# MiniSys.net
KiCad netlist of a schematic drawn in Altium Designer
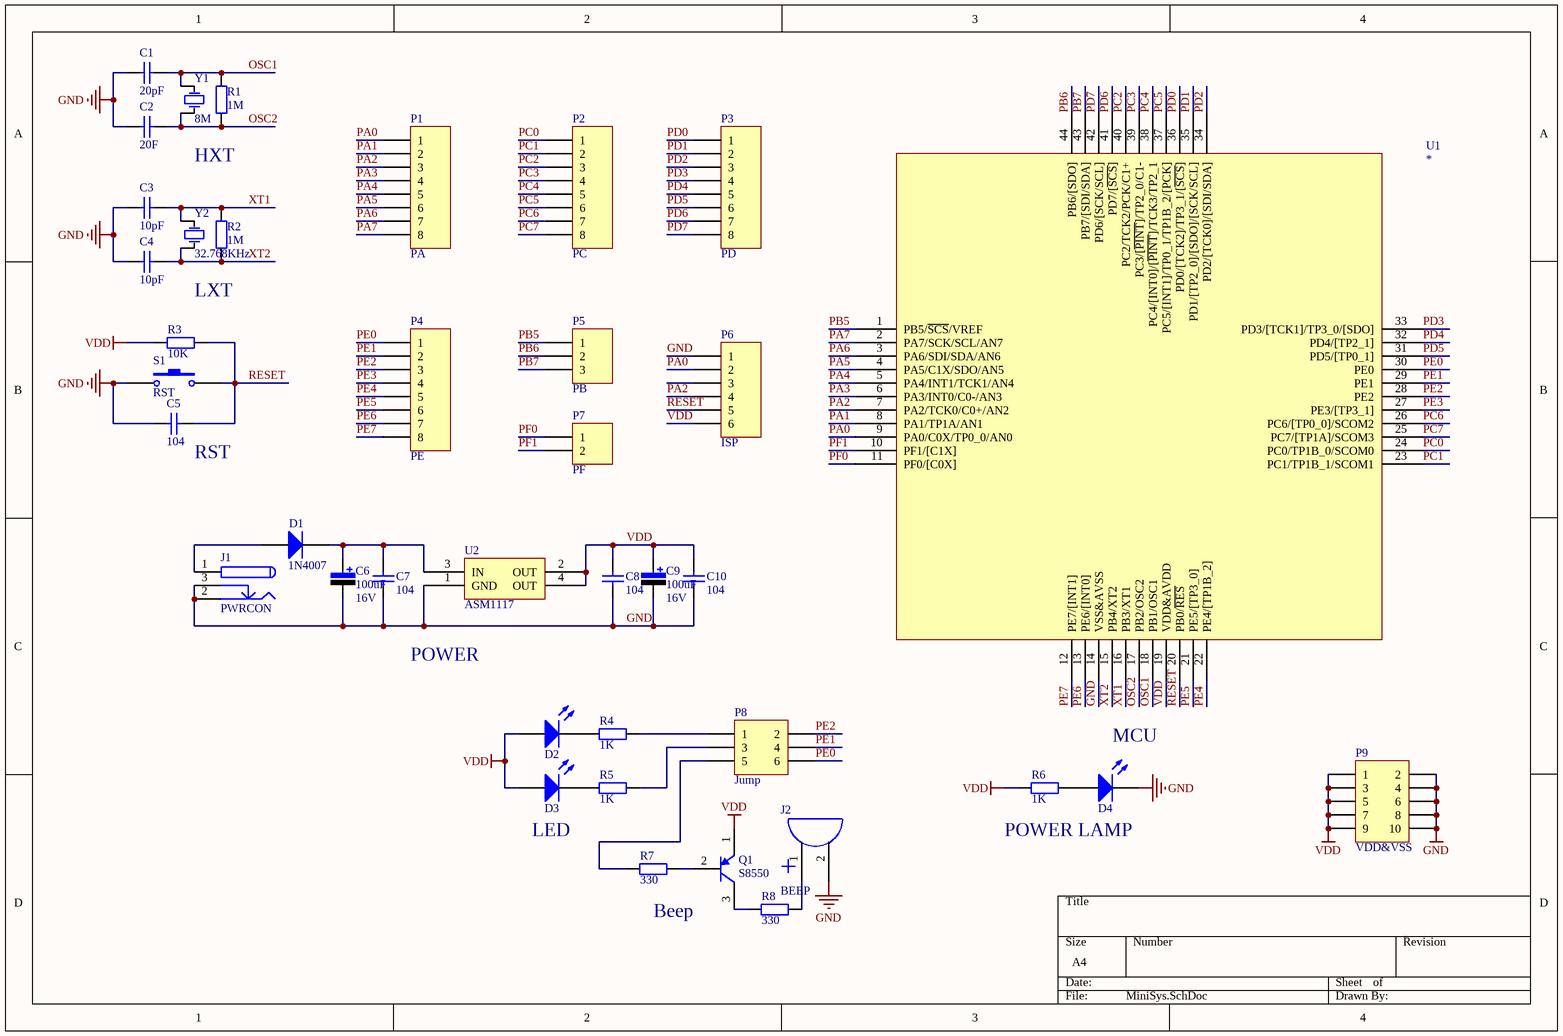
[diagram p0: MiniSys.SchDoc]

(export (version "E")
  (design (tool "Eeschema 10.0.6"))
  (components
    (comp (ref "C1")
      (value "20pF")
      (footprint "C-RAD-0805")
      (description "无极性电容")
      (fields (field (name "Comment") "Cap") (field (name "PUBLISHER") "Altium Limited"))
      (libsource (lib "Library") (part "Cap"))
    )
    (comp (ref "C2")
      (value "20F")
      (footprint "C-RAD-0805")
      (description "无极性电容")
      (fields (field (name "Comment") "Cap") (field (name "PUBLISHER") "Altium Limited"))
      (libsource (lib "Library") (part "Cap"))
    )
    (comp (ref "C3")
      (value "10pF")
      (footprint "C-RAD-0805")
      (description "无极性电容")
      (fields (field (name "Comment") "Cap") (field (name "PUBLISHER") "Altium Limited"))
      (libsource (lib "Library") (part "Cap"))
    )
    (comp (ref "C4")
      (value "10pF")
      (footprint "C-RAD-0805")
      (description "无极性电容")
      (fields (field (name "Comment") "Cap") (field (name "PUBLISHER") "Altium Limited"))
      (libsource (lib "Library") (part "Cap"))
    )
    (comp (ref "C5")
      (value "104")
      (footprint "C-RAD-0805")
      (description "无极性电容")
      (fields (field (name "Comment") "Cap") (field (name "PUBLISHER") "Altium Limited"))
      (libsource (lib "Library") (part "Cap"))
    )
    (comp (ref "C6")
      (value "100uF")
      (footprint "RB.1/.2")
      (description "极性电解电容")
      (fields
        (field (name "VOL") "16V")
        (field (name "Comment") "Cap Pol")
        (field (name "PUBLISHER") "Altium Limited")
      )
      (libsource (lib "Library") (part "Cap Pol"))
    )
    (comp (ref "C7")
      (value "104")
      (footprint "C-RAD-0805")
      (description "无极性电容")
      (fields (field (name "Comment") "Cap") (field (name "PUBLISHER") "Altium Limited"))
      (libsource (lib "Library") (part "Cap"))
    )
    (comp (ref "C8")
      (value "104")
      (footprint "C-RAD-0805")
      (description "无极性电容")
      (fields (field (name "Comment") "Cap") (field (name "PUBLISHER") "Altium Limited"))
      (libsource (lib "Library") (part "Cap"))
    )
    (comp (ref "C9")
      (value "100uF")
      (footprint "RB.1/.2")
      (description "极性电解电容")
      (fields
        (field (name "VOL") "16V")
        (field (name "Comment") "Cap Pol")
        (field (name "PUBLISHER") "Altium Limited")
      )
      (libsource (lib "Library") (part "Cap Pol"))
    )
    (comp (ref "C10")
      (value "104")
      (footprint "C-RAD-0805")
      (description "无极性电容")
      (fields (field (name "Comment") "Cap") (field (name "PUBLISHER") "Altium Limited"))
      (libsource (lib "Library") (part "Cap"))
    )
    (comp (ref "D1")
      (value "Diode")
      (footprint "DIODE-AXL")
      (description "二极管")
      (fields (field (name "TYPE") "1N4007") (field (name "PUBLISHER") "Altium Limited"))
      (libsource (lib "Library") (part "Diode"))
    )
    (comp (ref "D2")
      (value "LED0")
      (footprint "LED_0805")
      (description "发光二极管")
      (fields (field (name "PUBLISHER") "Altium Limited"))
      (libsource (lib "Library") (part "LED0"))
    )
    (comp (ref "D3")
      (value "LED0")
      (footprint "LED_0805")
      (description "发光二极管")
      (fields (field (name "PUBLISHER") "Altium Limited"))
      (libsource (lib "Library") (part "LED0"))
    )
    (comp (ref "D4")
      (value "LED0")
      (footprint "LED_0805")
      (description "发光二极管")
      (fields (field (name "PUBLISHER") "Altium Limited"))
      (libsource (lib "Library") (part "LED0"))
    )
    (comp (ref "J1")
      (value "PWRCON")
      (footprint "DC-005")
      (description "直流电源端子")
      (fields (field (name "PUBLISHER") "Altium Limited"))
      (libsource (lib "Library") (part "PWRCON"))
    )
    (comp (ref "J2")
      (value "BEEP")
      (footprint "Beep")
      (description "蜂鸣器")
      (libsource (lib "Library") (part "BEEP"))
    )
    (comp (ref "P1")
      (value "PA")
      (footprint "HDR1X8")
      (description "Header, 8-Pin")
      (fields (field (name "PUBLISHER") "Altium Limited"))
      (libsource (lib "Library") (part "Header 8"))
    )
    (comp (ref "P2")
      (value "PC")
      (footprint "HDR1X8")
      (description "Header, 8-Pin")
      (fields (field (name "PUBLISHER") "Altium Limited"))
      (libsource (lib "Library") (part "Header 8"))
    )
    (comp (ref "P3")
      (value "PD")
      (footprint "HDR1X8")
      (description "Header, 8-Pin")
      (fields (field (name "PUBLISHER") "Altium Limited"))
      (libsource (lib "Library") (part "Header 8"))
    )
    (comp (ref "P4")
      (value "PE")
      (footprint "HDR1X8")
      (description "Header, 8-Pin")
      (fields (field (name "PUBLISHER") "Altium Limited"))
      (libsource (lib "Library") (part "Header 8"))
    )
    (comp (ref "P5")
      (value "PB")
      (footprint "HDR3X1_A")
      (description "接插件")
      (fields (field (name "PUBLISHER") "Altium Limited"))
      (libsource (lib "Library") (part "Header 3"))
    )
    (comp (ref "P6")
      (value "ISP")
      (footprint "HDR1X6")
      (description "接插件")
      (fields (field (name "PUBLISHER") "Altium Limited"))
      (libsource (lib "Library") (part "Header 6"))
    )
    (comp (ref "P7")
      (value "PF")
      (footprint "HDR2X1_A")
      (description "接插件")
      (fields (field (name "PUBLISHER") "Altium Limited"))
      (libsource (lib "Library") (part "Header 2"))
    )
    (comp (ref "P8")
      (value "Jump")
      (footprint "HDR2X3")
      (description "Header, 3-Pin, Dual row")
      (fields (field (name "PUBLISHER") "Altium Limited"))
      (libsource (lib "Miscellaneous Connectors") (part "Header 3X2"))
    )
    (comp (ref "P9")
      (value "VDD&VSS")
      (footprint "HDR5X2_A1")
      (description "接插件")
      (fields (field (name "PUBLISHER") "Altium Limited"))
      (libsource (lib "Library") (part "Header 5X2"))
    )
    (comp (ref "Q1")
      (value "S8550")
      (footprint "TO-92A")
      (description "PNP三极管")
      (fields (field (name "PUBLISHER") "Altium Limited"))
      (libsource (lib "Library") (part "S8550"))
    )
    (comp (ref "R1")
      (value "1M")
      (footprint "0805-1")
      (description "贴片电阻")
      (fields (field (name "Comment") "Res1") (field (name "PUBLISHER") "Altium Limited"))
      (libsource (lib "Library") (part "Res1"))
    )
    (comp (ref "R2")
      (value "1M")
      (footprint "0805-1")
      (description "贴片电阻")
      (fields (field (name "Comment") "Res1") (field (name "PUBLISHER") "Altium Limited"))
      (libsource (lib "Library") (part "Res1"))
    )
    (comp (ref "R3")
      (value "10K")
      (footprint "0805-1")
      (description "贴片电阻")
      (fields (field (name "Comment") "Res1") (field (name "PUBLISHER") "Altium Limited"))
      (libsource (lib "") (part "Res1_2"))
    )
    (comp (ref "R4")
      (value "1K")
      (footprint "0805-1")
      (description "贴片电阻")
      (fields (field (name "Comment") "Res1") (field (name "PUBLISHER") "Altium Limited"))
      (libsource (lib "") (part "Res1_2"))
    )
    (comp (ref "R5")
      (value "1K")
      (footprint "0805-1")
      (description "贴片电阻")
      (fields (field (name "Comment") "Res1") (field (name "PUBLISHER") "Altium Limited"))
      (libsource (lib "") (part "Res1_2"))
    )
    (comp (ref "R6")
      (value "1K")
      (footprint "0805-1")
      (description "贴片电阻")
      (fields (field (name "Comment") "Res1") (field (name "PUBLISHER") "Altium Limited"))
      (libsource (lib "") (part "Res1_2"))
    )
    (comp (ref "R7")
      (value "330")
      (footprint "0805-1")
      (description "贴片电阻")
      (fields (field (name "Comment") "Res1") (field (name "PUBLISHER") "Altium Limited"))
      (libsource (lib "") (part "Res1_2"))
    )
    (comp (ref "R8")
      (value "330")
      (footprint "0805-1")
      (description "贴片电阻")
      (fields (field (name "Comment") "Res1") (field (name "PUBLISHER") "Altium Limited"))
      (libsource (lib "") (part "Res1_1"))
    )
    (comp (ref "S1")
      (value "RST")
      (footprint "BUTTON")
      (description "微动开关")
      (fields (field (name "PUBLISHER") "Altium Limited"))
      (libsource (lib "Library") (part "SW-PB"))
    )
    (comp (ref "U1")
      (value "*")
      (description "HT66F50 LQPF44")
      (fields (field (name "NAME") "*"))
      (libsource (lib "HT66FU50") (part "HT66FXXX"))
    )
    (comp (ref "U2")
      (value "ASM1117")
      (footprint "SOT-223")
      (description "3.3V稳压芯片")
      (libsource (lib "Library") (part "ASM1117"))
    )
    (comp (ref "Y1")
      (value "8M")
      (footprint "X-HC49U")
      (description "晶振")
      (fields (field (name "Comment") "XTAL") (field (name "PUBLISHER") "Altium Limited"))
      (libsource (lib "Library") (part "XTAL"))
    )
    (comp (ref "Y2")
      (value "32.768KHz")
      (footprint "X-TC15")
      (description "晶振")
      (fields (field (name "Comment") "XTAL") (field (name "PUBLISHER") "Altium Limited"))
      (libsource (lib "Library") (part "XTAL"))
    )
  )
  (nets
    (net (code "1") (name "/OSC1") (class "Default")
      (node (ref "C1") (pin "1") (pinfunction "1_1") (pintype "passive"))
      (node (ref "R1") (pin "1") (pinfunction "1_1") (pintype "passive"))
      (node (ref "U1") (pin "18") (pinfunction "PB1/OSC1_18") (pintype "passive"))
      (node (ref "Y1") (pin "1") (pinfunction "OSC1_1") (pintype "passive"))
    )
    (net (code "2") (name "/OSC2") (class "Default")
      (node (ref "C2") (pin "1") (pinfunction "1_1") (pintype "passive"))
      (node (ref "R1") (pin "2") (pinfunction "2_2") (pintype "passive"))
      (node (ref "U1") (pin "17") (pinfunction "PB2/OSC2_17") (pintype "passive"))
      (node (ref "Y1") (pin "2") (pinfunction "OSC2_2") (pintype "passive"))
    )
    (net (code "3") (name "/PA0") (class "Default")
      (node (ref "P1") (pin "1") (pinfunction "1_1") (pintype "passive"))
      (node (ref "P6") (pin "2") (pinfunction "2_2") (pintype "passive"))
      (node (ref "U1") (pin "9") (pinfunction "PA0/C0X/TP0_0/AN0_9") (pintype "passive"))
    )
    (net (code "4") (name "/PA1") (class "Default")
      (node (ref "P1") (pin "2") (pinfunction "2_2") (pintype "passive"))
      (node (ref "U1") (pin "8") (pinfunction "PA1/TP1A/AN1_8") (pintype "passive"))
    )
    (net (code "5") (name "/PA2") (class "Default")
      (node (ref "P1") (pin "3") (pinfunction "3_3") (pintype "passive"))
      (node (ref "P6") (pin "4") (pinfunction "4_4") (pintype "passive"))
      (node (ref "U1") (pin "7") (pinfunction "PA2/TCK0/C0+/AN2_7") (pintype "passive"))
    )
    (net (code "6") (name "/PA3") (class "Default")
      (node (ref "P1") (pin "4") (pinfunction "4_4") (pintype "passive"))
      (node (ref "U1") (pin "6") (pinfunction "PA3/INT0/C0-/AN3_6") (pintype "passive"))
    )
    (net (code "7") (name "/PA4") (class "Default")
      (node (ref "P1") (pin "5") (pinfunction "5_5") (pintype "passive"))
      (node (ref "U1") (pin "5") (pinfunction "PA4/INT1/TCK1/AN4_5") (pintype "passive"))
    )
    (net (code "8") (name "/PA5") (class "Default")
      (node (ref "P1") (pin "6") (pinfunction "6_6") (pintype "passive"))
      (node (ref "U1") (pin "4") (pinfunction "PA5/C1X/SDO/AN5_4") (pintype "passive"))
    )
    (net (code "9") (name "/PA6") (class "Default")
      (node (ref "P1") (pin "7") (pinfunction "7_7") (pintype "passive"))
      (node (ref "U1") (pin "3") (pinfunction "PA6/SDI/SDA/AN6_3") (pintype "passive"))
    )
    (net (code "10") (name "/PA7") (class "Default")
      (node (ref "P1") (pin "8") (pinfunction "8_8") (pintype "passive"))
      (node (ref "U1") (pin "2") (pinfunction "PA7/SCK/SCL/AN7_2") (pintype "passive"))
    )
    (net (code "11") (name "/PB5") (class "Default")
      (node (ref "P5") (pin "1") (pinfunction "1_1") (pintype "passive"))
      (node (ref "U1") (pin "1") (pinfunction "PB5/~{SCS}/VREF_1") (pintype "passive"))
    )
    (net (code "12") (name "/PB6") (class "Default")
      (node (ref "P5") (pin "2") (pinfunction "2_2") (pintype "passive"))
      (node (ref "U1") (pin "44") (pinfunction "PB6/[SDO]_44") (pintype "passive"))
    )
    (net (code "13") (name "/PB7") (class "Default")
      (node (ref "P5") (pin "3") (pinfunction "3_3") (pintype "passive"))
      (node (ref "U1") (pin "43") (pinfunction "PB7/[SDI/SDA]_43") (pintype "passive"))
    )
    (net (code "14") (name "/PC0") (class "Default")
      (node (ref "P2") (pin "1") (pinfunction "1_1") (pintype "passive"))
      (node (ref "U1") (pin "24") (pinfunction "PC0/TP1B_0/SCOM0_24") (pintype "passive"))
    )
    (net (code "15") (name "/PC1") (class "Default")
      (node (ref "P2") (pin "2") (pinfunction "2_2") (pintype "passive"))
      (node (ref "U1") (pin "23") (pinfunction "PC1/TP1B_1/SCOM1_23") (pintype "passive"))
    )
    (net (code "16") (name "/PC2") (class "Default")
      (node (ref "P2") (pin "3") (pinfunction "3_3") (pintype "passive"))
      (node (ref "U1") (pin "40") (pinfunction "PC2/TCK2/PCK/C1+_40") (pintype "passive"))
    )
    (net (code "17") (name "/PC3") (class "Default")
      (node (ref "P2") (pin "4") (pinfunction "4_4") (pintype "passive"))
      (node (ref "U1") (pin "39") (pinfunction "PC3/[~{PINT}]/TP2_0/C1-_39") (pintype "passive"))
    )
    (net (code "18") (name "/PC4") (class "Default")
      (node (ref "P2") (pin "5") (pinfunction "5_5") (pintype "passive"))
      (node (ref "U1") (pin "38") (pinfunction "PC4/[INT0]/[~{PINT}]/TCK3/TP2_1_38") (pintype "passive"))
    )
    (net (code "19") (name "/PC5") (class "Default")
      (node (ref "P2") (pin "6") (pinfunction "6_6") (pintype "passive"))
      (node (ref "U1") (pin "37") (pinfunction "PC5/[INT1]/TP0_1/TP1B_2/[PCK]_37") (pintype "passive"))
    )
    (net (code "20") (name "/PC6") (class "Default")
      (node (ref "P2") (pin "7") (pinfunction "7_7") (pintype "passive"))
      (node (ref "U1") (pin "26") (pinfunction "PC6/[TP0_0]/SCOM2_26") (pintype "passive"))
    )
    (net (code "21") (name "/PC7") (class "Default")
      (node (ref "P2") (pin "8") (pinfunction "8_8") (pintype "passive"))
      (node (ref "U1") (pin "25") (pinfunction "PC7/[TP1A]/SCOM3_25") (pintype "passive"))
    )
    (net (code "22") (name "/PD0") (class "Default")
      (node (ref "P3") (pin "1") (pinfunction "1_1") (pintype "passive"))
      (node (ref "U1") (pin "36") (pinfunction "PD0/[TCK2]/TP3_1/[~{SCS}]_36") (pintype "passive"))
    )
    (net (code "23") (name "/PD1") (class "Default")
      (node (ref "P3") (pin "2") (pinfunction "2_2") (pintype "passive"))
      (node (ref "U1") (pin "35") (pinfunction "PD1/[TP2_0]/[SDO]/[SCK/SCL]_35") (pintype "passive"))
    )
    (net (code "24") (name "/PD2") (class "Default")
      (node (ref "P3") (pin "3") (pinfunction "3_3") (pintype "passive"))
      (node (ref "U1") (pin "34") (pinfunction "PD2/[TCK0]/[SDI/SDA]_34") (pintype "passive"))
    )
    (net (code "25") (name "/PD3") (class "Default")
      (node (ref "P3") (pin "4") (pinfunction "4_4") (pintype "passive"))
      (node (ref "U1") (pin "33") (pinfunction "PD3/[TCK1]/TP3_0/[SDO]_33") (pintype "passive"))
    )
    (net (code "26") (name "/PD4") (class "Default")
      (node (ref "P3") (pin "5") (pinfunction "5_5") (pintype "passive"))
      (node (ref "U1") (pin "32") (pinfunction "PD4/[TP2_1]_32") (pintype "passive"))
    )
    (net (code "27") (name "/PD5") (class "Default")
      (node (ref "P3") (pin "6") (pinfunction "6_6") (pintype "passive"))
      (node (ref "U1") (pin "31") (pinfunction "PD5/[TP0_1]_31") (pintype "passive"))
    )
    (net (code "28") (name "/PD6") (class "Default")
      (node (ref "P3") (pin "7") (pinfunction "7_7") (pintype "passive"))
      (node (ref "U1") (pin "41") (pinfunction "PD7/[~{SCS}]_41") (pintype "passive"))
    )
    (net (code "29") (name "/PD7") (class "Default")
      (node (ref "P3") (pin "8") (pinfunction "8_8") (pintype "passive"))
      (node (ref "U1") (pin "42") (pinfunction "PD6/[SCK/SCL]_42") (pintype "passive"))
    )
    (net (code "30") (name "/PE0") (class "Default")
      (node (ref "P4") (pin "1") (pinfunction "1_1") (pintype "passive"))
      (node (ref "P8") (pin "6") (pinfunction "6_6") (pintype "passive"))
      (node (ref "U1") (pin "30") (pinfunction "PE0_30") (pintype "passive"))
    )
    (net (code "31") (name "/PE1") (class "Default")
      (node (ref "P4") (pin "2") (pinfunction "2_2") (pintype "passive"))
      (node (ref "P8") (pin "4") (pinfunction "4_4") (pintype "passive"))
      (node (ref "U1") (pin "29") (pinfunction "PE1_29") (pintype "passive"))
    )
    (net (code "32") (name "/PE2") (class "Default")
      (node (ref "P4") (pin "3") (pinfunction "3_3") (pintype "passive"))
      (node (ref "P8") (pin "2") (pinfunction "2_2") (pintype "passive"))
      (node (ref "U1") (pin "28") (pinfunction "PE2_28") (pintype "passive"))
    )
    (net (code "33") (name "/PE3") (class "Default")
      (node (ref "P4") (pin "4") (pinfunction "4_4") (pintype "passive"))
      (node (ref "U1") (pin "27") (pinfunction "PE3/[TP3_1]_27") (pintype "passive"))
    )
    (net (code "34") (name "/PE4") (class "Default")
      (node (ref "P4") (pin "5") (pinfunction "5_5") (pintype "passive"))
      (node (ref "U1") (pin "22") (pinfunction "PE4/[TP1B_2]_22") (pintype "passive"))
    )
    (net (code "35") (name "/PE5") (class "Default")
      (node (ref "P4") (pin "6") (pinfunction "6_6") (pintype "passive"))
      (node (ref "U1") (pin "21") (pinfunction "PE5/[TP3_0]_21") (pintype "passive"))
    )
    (net (code "36") (name "/PE6") (class "Default")
      (node (ref "P4") (pin "7") (pinfunction "7_7") (pintype "passive"))
      (node (ref "U1") (pin "13") (pinfunction "PE6/[INT0]_13") (pintype "passive"))
    )
    (net (code "37") (name "/PE7") (class "Default")
      (node (ref "P4") (pin "8") (pinfunction "8_8") (pintype "passive"))
      (node (ref "U1") (pin "12") (pinfunction "PE7/[INT1]_12") (pintype "passive"))
    )
    (net (code "38") (name "/PF0") (class "Default")
      (node (ref "P7") (pin "1") (pinfunction "1_1") (pintype "passive"))
      (node (ref "U1") (pin "11") (pinfunction "PF0/[C0X]_11") (pintype "passive"))
    )
    (net (code "39") (name "/PF1") (class "Default")
      (node (ref "P7") (pin "2") (pinfunction "2_2") (pintype "passive"))
      (node (ref "U1") (pin "10") (pinfunction "PF1/[C1X]_10") (pintype "passive"))
    )
    (net (code "40") (name "/RESET") (class "Default")
      (node (ref "C5") (pin "2") (pinfunction "2_2") (pintype "passive"))
      (node (ref "P6") (pin "5") (pinfunction "5_5") (pintype "passive"))
      (node (ref "R3") (pin "2") (pinfunction "2_2") (pintype "passive"))
      (node (ref "S1") (pin "2") (pinfunction "2_2") (pintype "passive"))
      (node (ref "U1") (pin "20") (pinfunction "PB0/~{RES}_20") (pintype "passive"))
    )
    (net (code "41") (name "/XT1") (class "Default")
      (node (ref "C3") (pin "1") (pinfunction "1_1") (pintype "passive"))
      (node (ref "R2") (pin "1") (pinfunction "1_1") (pintype "passive"))
      (node (ref "U1") (pin "16") (pinfunction "PB3/XT1_16") (pintype "passive"))
      (node (ref "Y2") (pin "1") (pinfunction "OSC1_1") (pintype "passive"))
    )
    (net (code "42") (name "/XT2") (class "Default")
      (node (ref "C4") (pin "1") (pinfunction "1_1") (pintype "passive"))
      (node (ref "R2") (pin "2") (pinfunction "2_2") (pintype "passive"))
      (node (ref "U1") (pin "15") (pinfunction "PB4/XT2_15") (pintype "passive"))
      (node (ref "Y2") (pin "2") (pinfunction "OSC2_2") (pintype "passive"))
    )
    (net (code "43") (name "GND") (class "Default")
      (node (ref "C1") (pin "2") (pinfunction "2_2") (pintype "passive"))
      (node (ref "C10") (pin "1") (pinfunction "1_1") (pintype "passive"))
      (node (ref "C2") (pin "2") (pinfunction "2_2") (pintype "passive"))
      (node (ref "C3") (pin "2") (pinfunction "2_2") (pintype "passive"))
      (node (ref "C4") (pin "2") (pinfunction "2_2") (pintype "passive"))
      (node (ref "C5") (pin "1") (pinfunction "1_1") (pintype "passive"))
      (node (ref "C6") (pin "2") (pinfunction "2_2") (pintype "passive"))
      (node (ref "C7") (pin "1") (pinfunction "1_1") (pintype "passive"))
      (node (ref "C8") (pin "1") (pinfunction "1_1") (pintype "passive"))
      (node (ref "C9") (pin "2") (pinfunction "2_2") (pintype "passive"))
      (node (ref "D4") (pin "2") (pinfunction "K_2") (pintype "passive"))
      (node (ref "J1") (pin "2") (pinfunction "2_2") (pintype "power_in"))
      (node (ref "J1") (pin "3") (pinfunction "3_3") (pintype "power_in"))
      (node (ref "J2") (pin "2") (pinfunction "1_2") (pintype "passive"))
      (node (ref "P6") (pin "1") (pinfunction "1_1") (pintype "passive"))
      (node (ref "P9") (pin "10") (pinfunction "10_10") (pintype "passive"))
      (node (ref "P9") (pin "2") (pinfunction "2_2") (pintype "passive"))
      (node (ref "P9") (pin "4") (pinfunction "4_4") (pintype "passive"))
      (node (ref "P9") (pin "6") (pinfunction "6_6") (pintype "passive"))
      (node (ref "P9") (pin "8") (pinfunction "8_8") (pintype "passive"))
      (node (ref "S1") (pin "1") (pinfunction "1_1") (pintype "passive"))
      (node (ref "U1") (pin "14") (pinfunction "VSS&AVSS_14") (pintype "passive"))
      (node (ref "U2") (pin "1") (pinfunction "GND_1") (pintype "passive"))
    )
    (net (code "44") (name "Net-(D1-A)") (class "Default")
      (node (ref "D1") (pin "1") (pinfunction "A_1") (pintype "passive"))
      (node (ref "J1") (pin "1") (pinfunction "1_1") (pintype "power_in"))
    )
    (net (code "45") (name "Net-(D1-K)") (class "Default")
      (node (ref "C6") (pin "1") (pinfunction "1_1") (pintype "passive"))
      (node (ref "C7") (pin "2") (pinfunction "2_2") (pintype "passive"))
      (node (ref "D1") (pin "2") (pinfunction "K_2") (pintype "passive"))
      (node (ref "U2") (pin "3") (pinfunction "IN_3") (pintype "passive"))
    )
    (net (code "46") (name "Net-(D2-K)") (class "Default")
      (node (ref "D2") (pin "2") (pinfunction "K_2") (pintype "passive"))
      (node (ref "R4") (pin "1") (pinfunction "1_1") (pintype "passive"))
    )
    (net (code "47") (name "Net-(D3-K)") (class "Default")
      (node (ref "D3") (pin "2") (pinfunction "K_2") (pintype "passive"))
      (node (ref "R5") (pin "1") (pinfunction "1_1") (pintype "passive"))
    )
    (net (code "48") (name "Net-(D4-A)") (class "Default")
      (node (ref "D4") (pin "1") (pinfunction "A_1") (pintype "passive"))
      (node (ref "R6") (pin "2") (pinfunction "2_2") (pintype "passive"))
    )
    (net (code "49") (name "Net-(J2-0)") (class "Default")
      (node (ref "J2") (pin "1") (pinfunction "0_1") (pintype "passive"))
      (node (ref "R8") (pin "1") (pinfunction "1_1") (pintype "passive"))
    )
    (net (code "50") (name "Net-(P8-Pad1)") (class "Default")
      (node (ref "P8") (pin "1") (pinfunction "1_1") (pintype "passive"))
      (node (ref "R4") (pin "2") (pinfunction "2_2") (pintype "passive"))
    )
    (net (code "51") (name "Net-(P8-Pad3)") (class "Default")
      (node (ref "P8") (pin "3") (pinfunction "3_3") (pintype "passive"))
      (node (ref "R5") (pin "2") (pinfunction "2_2") (pintype "passive"))
    )
    (net (code "52") (name "Net-(P8-Pad5)") (class "Default")
      (node (ref "P8") (pin "5") (pinfunction "5_5") (pintype "passive"))
      (node (ref "R7") (pin "1") (pinfunction "1_1") (pintype "passive"))
    )
    (net (code "53") (name "Net-(Q1-B)") (class "Default")
      (node (ref "Q1") (pin "2") (pinfunction "B_2") (pintype "passive"))
      (node (ref "R7") (pin "2") (pinfunction "2_2") (pintype "passive"))
    )
    (net (code "54") (name "Net-(Q1-C)") (class "Default")
      (node (ref "Q1") (pin "3") (pinfunction "C_3") (pintype "passive"))
      (node (ref "R8") (pin "2") (pinfunction "2_2") (pintype "passive"))
    )
    (net (code "55") (name "VDD") (class "Default")
      (node (ref "C10") (pin "2") (pinfunction "2_2") (pintype "passive"))
      (node (ref "C8") (pin "2") (pinfunction "2_2") (pintype "passive"))
      (node (ref "C9") (pin "1") (pinfunction "1_1") (pintype "passive"))
      (node (ref "D2") (pin "1") (pinfunction "A_1") (pintype "passive"))
      (node (ref "D3") (pin "1") (pinfunction "A_1") (pintype "passive"))
      (node (ref "P6") (pin "6") (pinfunction "6_6") (pintype "passive"))
      (node (ref "P9") (pin "1") (pinfunction "1_1") (pintype "passive"))
      (node (ref "P9") (pin "3") (pinfunction "3_3") (pintype "passive"))
      (node (ref "P9") (pin "5") (pinfunction "5_5") (pintype "passive"))
      (node (ref "P9") (pin "7") (pinfunction "7_7") (pintype "passive"))
      (node (ref "P9") (pin "9") (pinfunction "9_9") (pintype "passive"))
      (node (ref "Q1") (pin "1") (pinfunction "E_1") (pintype "passive"))
      (node (ref "R3") (pin "1") (pinfunction "1_1") (pintype "passive"))
      (node (ref "R6") (pin "1") (pinfunction "1_1") (pintype "passive"))
      (node (ref "U1") (pin "19") (pinfunction "VDD&AVDD_19") (pintype "passive"))
      (node (ref "U2") (pin "2") (pinfunction "OUT_2") (pintype "passive"))
      (node (ref "U2") (pin "4") (pinfunction "OUT_4") (pintype "passive"))
    )
    (net (code "56") (name "unconnected-(P6-Pad3)") (class "Default")
      (node (ref "P6") (pin "3") (pinfunction "3_3") (pintype "passive"))
    )
  )
)
